# pavapro3.net
KiCad netlist of a schematic drawn in EAGLE
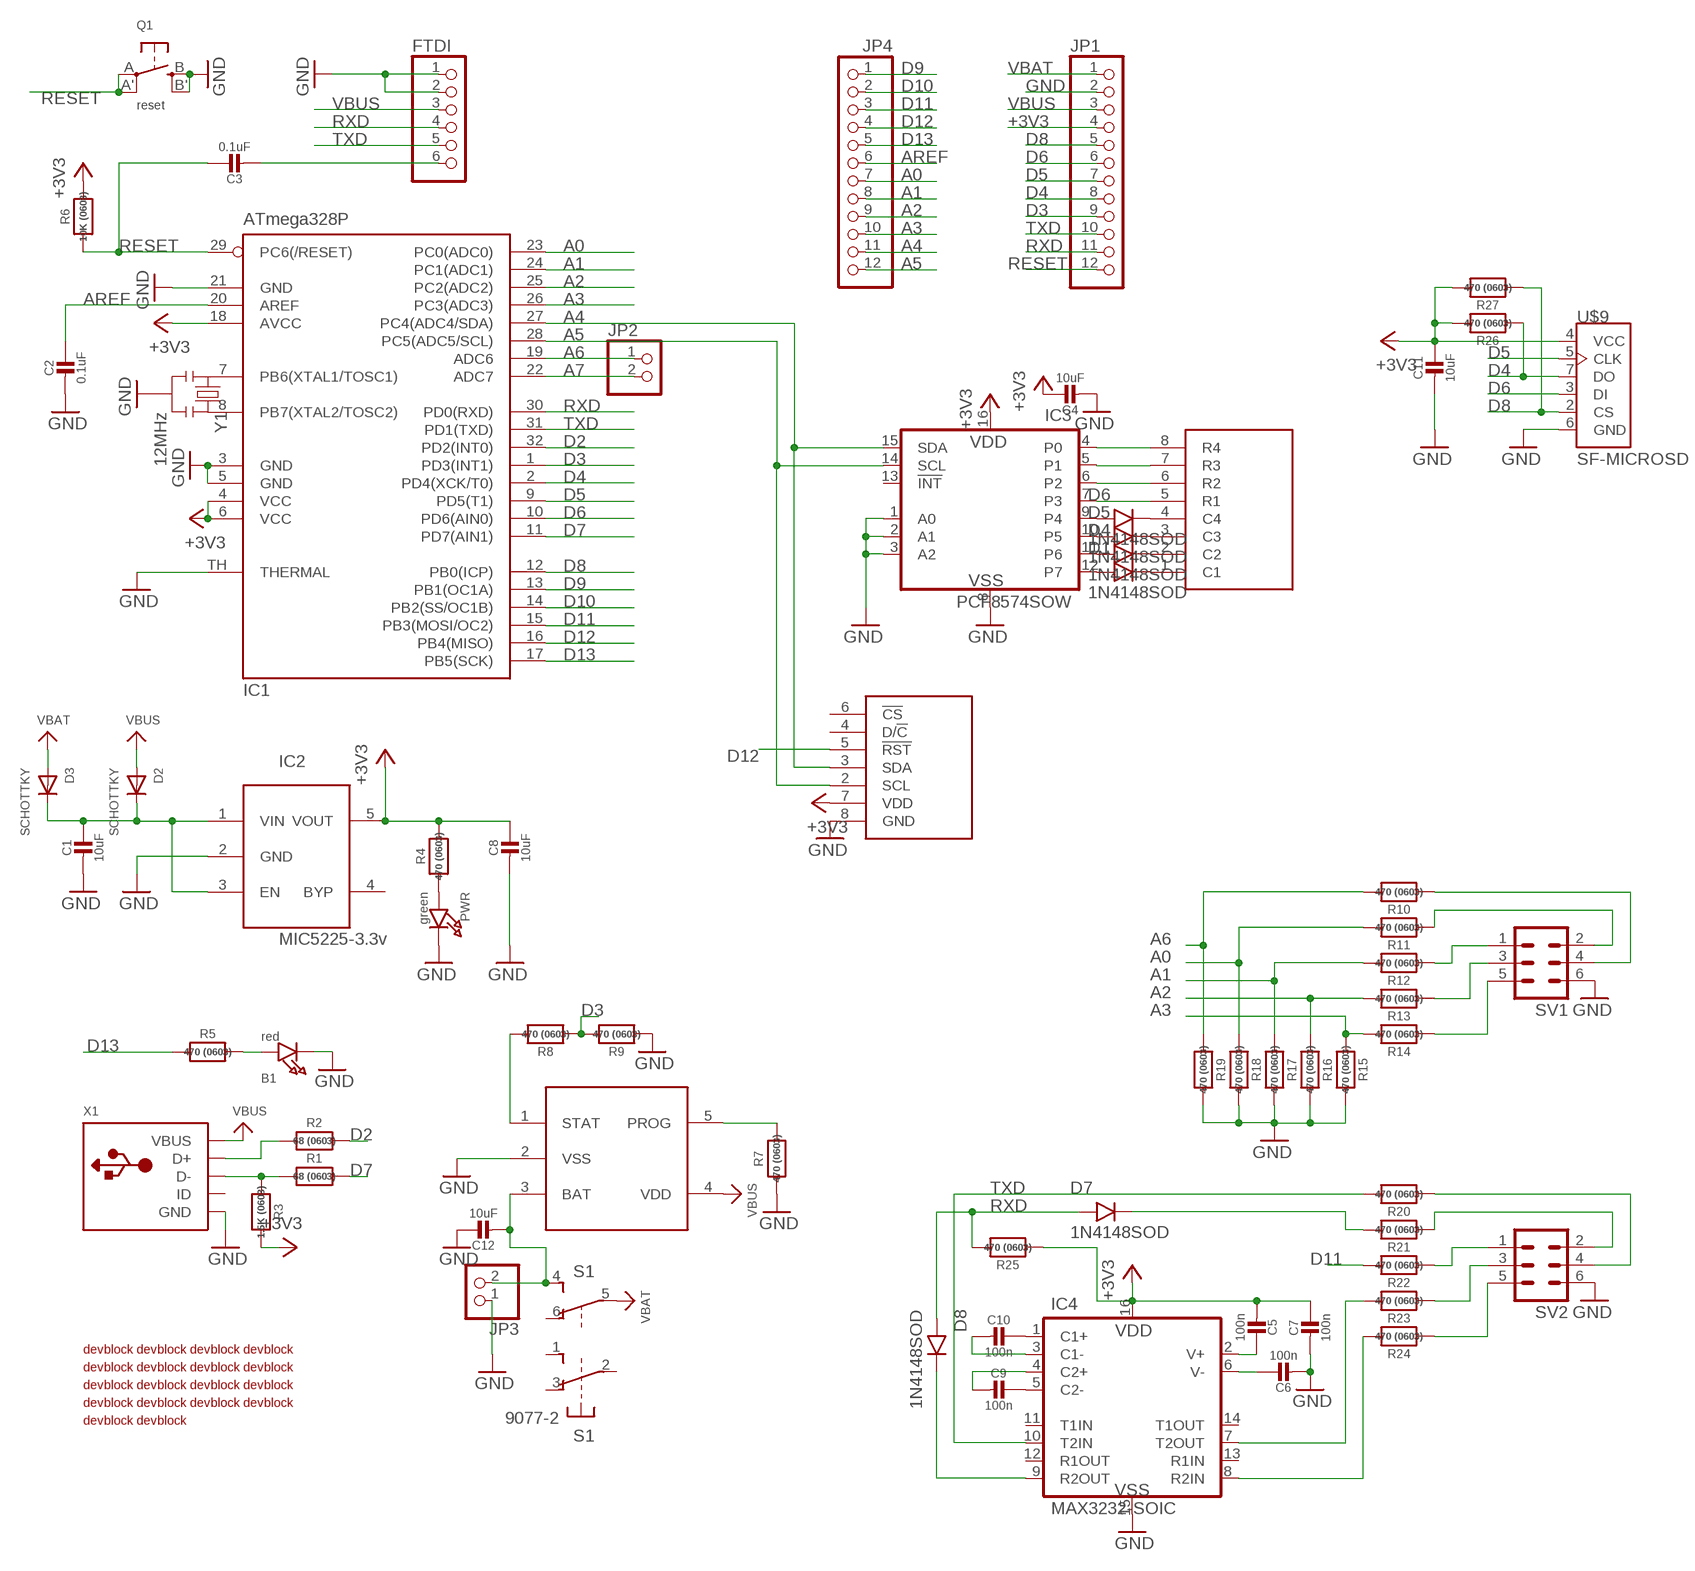
[diagram p0: schematic, sheet 1]

(export (version "E")
  (design (tool "Eeschema 10.0.6"))
  (components
    (comp (ref "B1")
      (value "red")
      (footprint "eagle-import:CHIPLED_0805_NOOUTLINE")
      (libsource (lib "eagle-import") (part "LED0805_NOOUTLINE"))
    )
    (comp (ref "C1")
      (value "10uF")
      (footprint "eagle-import:0805-NO")
      (libsource (lib "eagle-import") (part "CAP_CERAMIC0805-NOOUTLINE"))
    )
    (comp (ref "C2")
      (value "0.1uF")
      (footprint "eagle-import:_0805MP")
      (libsource (lib "eagle-import") (part "CAP_CERAMIC_0805MP"))
    )
    (comp (ref "C3")
      (value "0.1uF")
      (footprint "eagle-import:0805-NO")
      (libsource (lib "eagle-import") (part "CAP_CERAMIC0805-NOOUTLINE"))
    )
    (comp (ref "C4")
      (value "10uF")
      (footprint "eagle-import:0805-NO")
      (libsource (lib "eagle-import") (part "CAP_CERAMIC0805-NOOUTLINE"))
    )
    (comp (ref "C5")
      (value "100n")
      (footprint "eagle-import:0805-NO")
      (libsource (lib "eagle-import") (part "CAP_CERAMIC0805-NOOUTLINE"))
    )
    (comp (ref "C6")
      (value "100n")
      (footprint "eagle-import:0805-NO")
      (libsource (lib "eagle-import") (part "CAP_CERAMIC0805-NOOUTLINE"))
    )
    (comp (ref "C7")
      (value "100n")
      (footprint "eagle-import:0805-NO")
      (libsource (lib "eagle-import") (part "CAP_CERAMIC0805-NOOUTLINE"))
    )
    (comp (ref "C8")
      (value "10uF")
      (footprint "eagle-import:0805-NO")
      (libsource (lib "eagle-import") (part "CAP_CERAMIC0805-NOOUTLINE"))
    )
    (comp (ref "C9")
      (value "100n")
      (footprint "eagle-import:0805-NO")
      (libsource (lib "eagle-import") (part "CAP_CERAMIC0805-NOOUTLINE"))
    )
    (comp (ref "C10")
      (value "100n")
      (footprint "eagle-import:0805-NO")
      (libsource (lib "eagle-import") (part "CAP_CERAMIC0805-NOOUTLINE"))
    )
    (comp (ref "C11")
      (value "10uF")
      (footprint "eagle-import:0805-NO")
      (libsource (lib "eagle-import") (part "CAP_CERAMIC0805-NOOUTLINE"))
    )
    (comp (ref "C12")
      (value "10uF")
      (footprint "eagle-import:0805-NO")
      (libsource (lib "eagle-import") (part "CAP_CERAMIC0805-NOOUTLINE"))
    )
    (comp (ref "D1")
      (value "1N4148SOD")
      (footprint "eagle-import:SOD-80")
      (libsource (lib "eagle-import") (part "1N4148SOD"))
    )
    (comp (ref "D2")
      (value "SCHOTTKY")
      (footprint "eagle-import:ADAFRUIT_SOD-123FL")
      (libsource (lib "eagle-import") (part "ADAFRUIT_DIODE_SOD-123FL"))
    )
    (comp (ref "D3")
      (value "SCHOTTKY")
      (footprint "eagle-import:ADAFRUIT_SOD-123FL")
      (libsource (lib "eagle-import") (part "ADAFRUIT_DIODE_SOD-123FL"))
    )
    (comp (ref "D4")
      (value "1N4148SOD")
      (footprint "eagle-import:SOD-80")
      (libsource (lib "eagle-import") (part "1N4148SOD"))
    )
    (comp (ref "D5")
      (value "1N4148SOD")
      (footprint "eagle-import:SOD-80")
      (libsource (lib "eagle-import") (part "1N4148SOD"))
    )
    (comp (ref "D6")
      (value "1N4148SOD")
      (footprint "eagle-import:SOD-80")
      (libsource (lib "eagle-import") (part "1N4148SOD"))
    )
    (comp (ref "D7")
      (value "1N4148SOD")
      (footprint "eagle-import:SOD-80")
      (libsource (lib "eagle-import") (part "1N4148SOD"))
    )
    (comp (ref "D8")
      (value "1N4148SOD")
      (footprint "eagle-import:SOD-80")
      (libsource (lib "eagle-import") (part "1N4148SOD"))
    )
    (comp (ref "FTDI")
      (value "ADAFRUIT_PINHD-1X6CB")
      (footprint "eagle-import:ADAFRUIT_1X06-CLEANBIG")
      (libsource (lib "eagle-import") (part "ADAFRUIT_PINHD-1X6CB"))
    )
    (comp (ref "IC1")
      (value "ATmega328P")
      (footprint "eagle-import:MLF32-TH")
      (fields (field (name "MPN") "ATMEGA88PA-MU"))
      (libsource (lib "eagle-import") (part "MEGA8-MI"))
    )
    (comp (ref "IC2")
      (value "MIC5225-3.3v")
      (footprint "eagle-import:SOT23-5L")
      (libsource (lib "eagle-import") (part "LP298XS"))
    )
    (comp (ref "IC3")
      (value "PCF8574SOW")
      (footprint "eagle-import:SO-16DW")
      (libsource (lib "eagle-import") (part "PCF8574SOW"))
    )
    (comp (ref "IC4")
      (value "MAX3232-SOIC")
      (footprint "eagle-import:SO-16")
      (libsource (lib "eagle-import") (part "MAX3232-SOIC"))
    )
    (comp (ref "JP1")
      (value "ADAFRUIT_PINHD-1X12-CB")
      (footprint "eagle-import:ADAFRUIT_1X12-CB")
      (libsource (lib "eagle-import") (part "ADAFRUIT_PINHD-1X12-CB"))
    )
    (comp (ref "JP2")
      (value "HEADER-1X2ROUND")
      (footprint "eagle-import:1X02_ROUND")
      (libsource (lib "eagle-import") (part "HEADER-1X2ROUND"))
    )
    (comp (ref "JP3")
      (value "PINHD-1X02_2.54-90°")
      (footprint "eagle-import:1X02_90")
      (libsource (lib "eagle-import") (part "PINHD-1X02_2.54-90°"))
    )
    (comp (ref "JP4")
      (value "ADAFRUIT_PINHD-1X12-CB")
      (footprint "eagle-import:ADAFRUIT_1X12-CB")
      (libsource (lib "eagle-import") (part "ADAFRUIT_PINHD-1X12-CB"))
    )
    (comp (ref "PWR")
      (value "green")
      (footprint "eagle-import:CHIPLED_0805_NOOUTLINE")
      (libsource (lib "eagle-import") (part "LED0805_NOOUTLINE"))
    )
    (comp (ref "Q1")
      (value "reset")
      (footprint "eagle-import:BTN_KMR2_4.6X2.8")
      (libsource (lib "eagle-import") (part "SWITCH_TACT_SMT4.6X2.8"))
    )
    (comp (ref "R1")
      (value "68 (0603)")
      (footprint "eagle-import:0603-NO")
      (libsource (lib "eagle-import") (part "RESISTOR_0603_NOOUT"))
    )
    (comp (ref "R2")
      (value "68 (0603)")
      (footprint "eagle-import:0603-NO")
      (libsource (lib "eagle-import") (part "RESISTOR_0603_NOOUT"))
    )
    (comp (ref "R3")
      (value "1.5K (0603)")
      (footprint "eagle-import:0603-NO")
      (libsource (lib "eagle-import") (part "RESISTOR_0603_NOOUT"))
    )
    (comp (ref "R4")
      (value "470 (0603)")
      (footprint "eagle-import:0603-NO")
      (libsource (lib "eagle-import") (part "RESISTOR_0603_NOOUT"))
    )
    (comp (ref "R5")
      (value "470 (0603)")
      (footprint "eagle-import:0603-NO")
      (libsource (lib "eagle-import") (part "RESISTOR_0603_NOOUT"))
    )
    (comp (ref "R6")
      (value "10K (0603)")
      (footprint "eagle-import:0805-NO")
      (libsource (lib "eagle-import") (part "RESISTOR0805_NOOUTLINE"))
    )
    (comp (ref "R7")
      (value "470 (0603)")
      (footprint "eagle-import:_0805")
      (libsource (lib "eagle-import") (part "RESISTOR_0805"))
    )
    (comp (ref "R8")
      (value "470 (0603)")
      (footprint "eagle-import:_0805")
      (libsource (lib "eagle-import") (part "RESISTOR_0805"))
    )
    (comp (ref "R9")
      (value "470 (0603)")
      (footprint "eagle-import:_0805")
      (libsource (lib "eagle-import") (part "RESISTOR_0805"))
    )
    (comp (ref "R10")
      (value "470 (0603)")
      (footprint "eagle-import:_0805")
      (libsource (lib "eagle-import") (part "RESISTOR_0805"))
    )
    (comp (ref "R11")
      (value "470 (0603)")
      (footprint "eagle-import:_0805")
      (libsource (lib "eagle-import") (part "RESISTOR_0805"))
    )
    (comp (ref "R12")
      (value "470 (0603)")
      (footprint "eagle-import:_0805")
      (libsource (lib "eagle-import") (part "RESISTOR_0805"))
    )
    (comp (ref "R13")
      (value "470 (0603)")
      (footprint "eagle-import:_0805")
      (libsource (lib "eagle-import") (part "RESISTOR_0805"))
    )
    (comp (ref "R14")
      (value "470 (0603)")
      (footprint "eagle-import:_0805")
      (libsource (lib "eagle-import") (part "RESISTOR_0805"))
    )
    (comp (ref "R15")
      (value "470 (0603)")
      (footprint "eagle-import:_0805")
      (libsource (lib "eagle-import") (part "RESISTOR_0805"))
    )
    (comp (ref "R16")
      (value "470 (0603)")
      (footprint "eagle-import:_0805")
      (libsource (lib "eagle-import") (part "RESISTOR_0805"))
    )
    (comp (ref "R17")
      (value "470 (0603)")
      (footprint "eagle-import:_0805")
      (libsource (lib "eagle-import") (part "RESISTOR_0805"))
    )
    (comp (ref "R18")
      (value "470 (0603)")
      (footprint "eagle-import:_0805")
      (libsource (lib "eagle-import") (part "RESISTOR_0805"))
    )
    (comp (ref "R19")
      (value "470 (0603)")
      (footprint "eagle-import:_0805")
      (libsource (lib "eagle-import") (part "RESISTOR_0805"))
    )
    (comp (ref "R20")
      (value "470 (0603)")
      (footprint "eagle-import:_0805")
      (libsource (lib "eagle-import") (part "RESISTOR_0805"))
    )
    (comp (ref "R21")
      (value "470 (0603)")
      (footprint "eagle-import:_0805")
      (libsource (lib "eagle-import") (part "RESISTOR_0805"))
    )
    (comp (ref "R22")
      (value "470 (0603)")
      (footprint "eagle-import:_0805")
      (libsource (lib "eagle-import") (part "RESISTOR_0805"))
    )
    (comp (ref "R23")
      (value "470 (0603)")
      (footprint "eagle-import:_0805")
      (libsource (lib "eagle-import") (part "RESISTOR_0805"))
    )
    (comp (ref "R24")
      (value "470 (0603)")
      (footprint "eagle-import:_0805")
      (libsource (lib "eagle-import") (part "RESISTOR_0805"))
    )
    (comp (ref "R25")
      (value "470 (0603)")
      (footprint "eagle-import:_0805")
      (libsource (lib "eagle-import") (part "RESISTOR_0805"))
    )
    (comp (ref "R26")
      (value "470 (0603)")
      (footprint "eagle-import:_0805")
      (libsource (lib "eagle-import") (part "RESISTOR_0805"))
    )
    (comp (ref "R27")
      (value "470 (0603)")
      (footprint "eagle-import:_0805")
      (libsource (lib "eagle-import") (part "RESISTOR_0805"))
    )
    (comp (ref "S1")
      (value "9077-2")
      (footprint "eagle-import:9077-2")
      (libsource (lib "eagle-import") (part "9077-2"))
    )
    (comp (ref "SV1")
      (value "ML6")
      (footprint "eagle-import:ML6")
      (libsource (lib "eagle-import") (part "ML6"))
    )
    (comp (ref "SV2")
      (value "ML6")
      (footprint "eagle-import:ML6")
      (libsource (lib "eagle-import") (part "ML6"))
    )
    (comp (ref "U$5")
      (value "DISP_OLED_2864")
      (footprint "eagle-import:OLED2864")
      (libsource (lib "eagle-import") (part "DISP_OLED_2864"))
    )
    (comp (ref "U$6")
      (value "MCP73831")
      (footprint "eagle-import:SOT23-5")
      (libsource (lib "eagle-import") (part "MCP73831"))
    )
    (comp (ref "U$7")
      (value "KB1604")
      (footprint "eagle-import:KB1604")
      (libsource (lib "eagle-import") (part "KB1604"))
    )
    (comp (ref "U$9")
      (value "SF-MICROSD")
      (footprint "eagle-import:MICROSD")
      (libsource (lib "eagle-import") (part "SF-MICROSD"))
    )
    (comp (ref "U$10")
      (value "DEVBLOCK_1_16")
      (footprint "eagle-import:DEVBLOCK_1_16")
      (libsource (lib "eagle-import") (part "DEVBLOCK_1_16"))
    )
    (comp (ref "U$11")
      (value "DEVBLOCK_1_16")
      (footprint "eagle-import:DEVBLOCK_1_16")
      (libsource (lib "eagle-import") (part "DEVBLOCK_1_16"))
    )
    (comp (ref "U$12")
      (value "DEVBLOCK_1_16")
      (footprint "eagle-import:DEVBLOCK_1_16")
      (libsource (lib "eagle-import") (part "DEVBLOCK_1_16"))
    )
    (comp (ref "U$13")
      (value "DEVBLOCK_1_16")
      (footprint "eagle-import:DEVBLOCK_1_16")
      (libsource (lib "eagle-import") (part "DEVBLOCK_1_16"))
    )
    (comp (ref "U$14")
      (value "DEVBLOCK_1_16")
      (footprint "eagle-import:DEVBLOCK_1_16")
      (libsource (lib "eagle-import") (part "DEVBLOCK_1_16"))
    )
    (comp (ref "U$15")
      (value "DEVBLOCK_1_16")
      (footprint "eagle-import:DEVBLOCK_1_16")
      (libsource (lib "eagle-import") (part "DEVBLOCK_1_16"))
    )
    (comp (ref "U$16")
      (value "DEVBLOCK_1_16")
      (footprint "eagle-import:DEVBLOCK_1_16")
      (libsource (lib "eagle-import") (part "DEVBLOCK_1_16"))
    )
    (comp (ref "U$17")
      (value "DEVBLOCK_1_16")
      (footprint "eagle-import:DEVBLOCK_1_16")
      (libsource (lib "eagle-import") (part "DEVBLOCK_1_16"))
    )
    (comp (ref "U$18")
      (value "DEVBLOCK_1_16")
      (footprint "eagle-import:DEVBLOCK_1_16")
      (libsource (lib "eagle-import") (part "DEVBLOCK_1_16"))
    )
    (comp (ref "U$19")
      (value "DEVBLOCK_1_16")
      (footprint "eagle-import:DEVBLOCK_1_16")
      (libsource (lib "eagle-import") (part "DEVBLOCK_1_16"))
    )
    (comp (ref "U$20")
      (value "DEVBLOCK_1_16")
      (footprint "eagle-import:DEVBLOCK_1_16")
      (libsource (lib "eagle-import") (part "DEVBLOCK_1_16"))
    )
    (comp (ref "U$21")
      (value "DEVBLOCK_1_16")
      (footprint "eagle-import:DEVBLOCK_1_16")
      (libsource (lib "eagle-import") (part "DEVBLOCK_1_16"))
    )
    (comp (ref "U$22")
      (value "DEVBLOCK_1_16")
      (footprint "eagle-import:DEVBLOCK_1_16")
      (libsource (lib "eagle-import") (part "DEVBLOCK_1_16"))
    )
    (comp (ref "U$23")
      (value "DEVBLOCK_1_16")
      (footprint "eagle-import:DEVBLOCK_1_16")
      (libsource (lib "eagle-import") (part "DEVBLOCK_1_16"))
    )
    (comp (ref "U$24")
      (value "DEVBLOCK_1_16")
      (footprint "eagle-import:DEVBLOCK_1_16")
      (libsource (lib "eagle-import") (part "DEVBLOCK_1_16"))
    )
    (comp (ref "U$25")
      (value "DEVBLOCK_1_16")
      (footprint "eagle-import:DEVBLOCK_1_16")
      (libsource (lib "eagle-import") (part "DEVBLOCK_1_16"))
    )
    (comp (ref "U$26")
      (value "DEVBLOCK_1_16")
      (footprint "eagle-import:DEVBLOCK_1_16")
      (libsource (lib "eagle-import") (part "DEVBLOCK_1_16"))
    )
    (comp (ref "U$27")
      (value "DEVBLOCK_1_16")
      (footprint "eagle-import:DEVBLOCK_1_16")
      (libsource (lib "eagle-import") (part "DEVBLOCK_1_16"))
    )
    (comp (ref "X1")
      (value "MICROBUILDER_USBMICRO_20329")
      (footprint "eagle-import:MICROBUILDER_4UCONN_20329")
      (libsource (lib "eagle-import") (part "MICROBUILDER_USBMICRO_20329"))
    )
    (comp (ref "Y1")
      (value "12MHz")
      (footprint "eagle-import:RESONATOR-SMD")
      (libsource (lib "eagle-import") (part "RESONATORSMD"))
    )
  )
  (nets
    (net (code "1") (name "+3V3") (class "Default")
      (node (ref "C11") (pin "1") (pinfunction "1_1") (pintype "passive"))
      (node (ref "C4") (pin "1") (pinfunction "1_1") (pintype "passive"))
      (node (ref "C5") (pin "2") (pinfunction "2_2") (pintype "passive"))
      (node (ref "C7") (pin "1") (pinfunction "1_1") (pintype "passive"))
      (node (ref "C8") (pin "1") (pinfunction "1_1") (pintype "passive"))
      (node (ref "IC1") (pin "18") (pinfunction "AVCC_18") (pintype "power_in"))
      (node (ref "IC1") (pin "4") (pinfunction "VCC_4") (pintype "power_in"))
      (node (ref "IC1") (pin "6") (pinfunction "VCC_6") (pintype "power_in"))
      (node (ref "IC2") (pin "5") (pinfunction "VOUT_5") (pintype "bidirectional"))
      (node (ref "IC3") (pin "16") (pinfunction "VDD_16") (pintype "power_in"))
      (node (ref "IC4") (pin "16") (pinfunction "VDD_16") (pintype "power_in"))
      (node (ref "JP1") (pin "4") (pinfunction "4_4") (pintype "passive"))
      (node (ref "R25") (pin "2") (pinfunction "2_2") (pintype "passive"))
      (node (ref "R26") (pin "1") (pinfunction "1_1") (pintype "passive"))
      (node (ref "R27") (pin "1") (pinfunction "1_1") (pintype "passive"))
      (node (ref "R3") (pin "2") (pinfunction "2_2") (pintype "passive"))
      (node (ref "R4") (pin "2") (pinfunction "2_2") (pintype "passive"))
      (node (ref "R6") (pin "2") (pinfunction "2_2") (pintype "passive"))
      (node (ref "U$5") (pin "7") (pinfunction "VDD_7") (pintype "bidirectional"))
      (node (ref "U$9") (pin "4") (pinfunction "VCC_4") (pintype "passive"))
    )
    (net (code "2") (name "/A0") (class "Default")
      (node (ref "IC1") (pin "23") (pinfunction "PC0(ADC0)_23") (pintype "bidirectional"))
      (node (ref "JP4") (pin "7") (pinfunction "7_7") (pintype "passive"))
      (node (ref "R11") (pin "1") (pinfunction "1_1") (pintype "passive"))
      (node (ref "R18") (pin "2") (pinfunction "2_2") (pintype "passive"))
    )
    (net (code "3") (name "/A1") (class "Default")
      (node (ref "IC1") (pin "24") (pinfunction "PC1(ADC1)_24") (pintype "bidirectional"))
      (node (ref "JP4") (pin "8") (pinfunction "8_8") (pintype "passive"))
      (node (ref "R12") (pin "1") (pinfunction "1_1") (pintype "passive"))
      (node (ref "R17") (pin "2") (pinfunction "2_2") (pintype "passive"))
    )
    (net (code "4") (name "/A2") (class "Default")
      (node (ref "IC1") (pin "25") (pinfunction "PC2(ADC2)_25") (pintype "bidirectional"))
      (node (ref "JP4") (pin "9") (pinfunction "9_9") (pintype "passive"))
      (node (ref "R13") (pin "1") (pinfunction "1_1") (pintype "passive"))
      (node (ref "R16") (pin "2") (pinfunction "2_2") (pintype "passive"))
    )
    (net (code "5") (name "/A3") (class "Default")
      (node (ref "IC1") (pin "26") (pinfunction "PC3(ADC3)_26") (pintype "bidirectional"))
      (node (ref "JP4") (pin "10") (pinfunction "10_10") (pintype "passive"))
      (node (ref "R14") (pin "1") (pinfunction "1_1") (pintype "passive"))
      (node (ref "R15") (pin "2") (pinfunction "2_2") (pintype "passive"))
    )
    (net (code "6") (name "/A4") (class "Default")
      (node (ref "IC1") (pin "27") (pinfunction "PC4(ADC4/SDA)_27") (pintype "bidirectional"))
      (node (ref "IC3") (pin "15") (pinfunction "SDA_15") (pintype "bidirectional"))
      (node (ref "JP4") (pin "11") (pinfunction "11_11") (pintype "passive"))
      (node (ref "U$5") (pin "3") (pinfunction "SDA_3") (pintype "bidirectional"))
    )
    (net (code "7") (name "/A5") (class "Default")
      (node (ref "IC1") (pin "28") (pinfunction "PC5(ADC5/SCL)_28") (pintype "bidirectional"))
      (node (ref "IC3") (pin "14") (pinfunction "SCL_14") (pintype "bidirectional"))
      (node (ref "JP4") (pin "12") (pinfunction "12_12") (pintype "passive"))
      (node (ref "U$5") (pin "2") (pinfunction "SCL_2") (pintype "bidirectional"))
    )
    (net (code "8") (name "/A6") (class "Default")
      (node (ref "IC1") (pin "19") (pinfunction "ADC6_19") (pintype "bidirectional"))
      (node (ref "JP2") (pin "1") (pinfunction "1_1") (pintype "passive"))
      (node (ref "R10") (pin "1") (pinfunction "1_1") (pintype "passive"))
      (node (ref "R19") (pin "2") (pinfunction "2_2") (pintype "passive"))
    )
    (net (code "9") (name "/A7") (class "Default")
      (node (ref "IC1") (pin "22") (pinfunction "ADC7_22") (pintype "bidirectional"))
      (node (ref "JP2") (pin "2") (pinfunction "2_2") (pintype "passive"))
    )
    (net (code "10") (name "/AREF") (class "Default")
      (node (ref "C2") (pin "1") (pinfunction "1_1") (pintype "passive"))
      (node (ref "IC1") (pin "20") (pinfunction "AREF_20") (pintype "passive"))
      (node (ref "JP4") (pin "6") (pinfunction "6_6") (pintype "passive"))
    )
    (net (code "11") (name "/D2") (class "Default")
      (node (ref "IC1") (pin "32") (pinfunction "PD2(INT0)_32") (pintype "bidirectional"))
      (node (ref "R2") (pin "2") (pinfunction "2_2") (pintype "passive"))
    )
    (net (code "12") (name "/D3") (class "Default")
      (node (ref "IC1") (pin "1") (pinfunction "PD3(INT1)_1") (pintype "bidirectional"))
      (node (ref "JP1") (pin "9") (pinfunction "9_9") (pintype "passive"))
      (node (ref "R8") (pin "2") (pinfunction "2_2") (pintype "passive"))
      (node (ref "R9") (pin "1") (pinfunction "1_1") (pintype "passive"))
    )
    (net (code "13") (name "/D4") (class "Default")
      (node (ref "IC1") (pin "2") (pinfunction "PD4(XCK/T0)_2") (pintype "bidirectional"))
      (node (ref "JP1") (pin "8") (pinfunction "8_8") (pintype "passive"))
      (node (ref "R26") (pin "2") (pinfunction "2_2") (pintype "passive"))
      (node (ref "U$9") (pin "7") (pinfunction "DO_7") (pintype "bidirectional"))
    )
    (net (code "14") (name "/D5") (class "Default")
      (node (ref "IC1") (pin "9") (pinfunction "PD5(T1)_9") (pintype "bidirectional"))
      (node (ref "JP1") (pin "7") (pinfunction "7_7") (pintype "passive"))
      (node (ref "U$9") (pin "5") (pinfunction "CLK_5") (pintype "bidirectional"))
    )
    (net (code "15") (name "/D6") (class "Default")
      (node (ref "IC1") (pin "10") (pinfunction "PD6(AIN0)_10") (pintype "bidirectional"))
      (node (ref "JP1") (pin "6") (pinfunction "6_6") (pintype "passive"))
      (node (ref "U$9") (pin "3") (pinfunction "DI_3") (pintype "bidirectional"))
    )
    (net (code "16") (name "/D7") (class "Default")
      (node (ref "IC1") (pin "11") (pinfunction "PD7(AIN1)_11") (pintype "bidirectional"))
      (node (ref "R1") (pin "2") (pinfunction "2_2") (pintype "passive"))
    )
    (net (code "17") (name "/D8") (class "Default")
      (node (ref "IC1") (pin "12") (pinfunction "PB0(ICP)_12") (pintype "bidirectional"))
      (node (ref "JP1") (pin "5") (pinfunction "5_5") (pintype "passive"))
      (node (ref "R27") (pin "2") (pinfunction "2_2") (pintype "passive"))
      (node (ref "U$9") (pin "2") (pinfunction "CS_2") (pintype "bidirectional"))
    )
    (net (code "18") (name "/D9") (class "Default")
      (node (ref "IC1") (pin "13") (pinfunction "PB1(OC1A)_13") (pintype "bidirectional"))
      (node (ref "JP4") (pin "1") (pinfunction "1_1") (pintype "passive"))
    )
    (net (code "19") (name "/D10") (class "Default")
      (node (ref "IC1") (pin "14") (pinfunction "PB2(SS/OC1B)_14") (pintype "bidirectional"))
      (node (ref "JP4") (pin "2") (pinfunction "2_2") (pintype "passive"))
    )
    (net (code "20") (name "/D11") (class "Default")
      (node (ref "IC1") (pin "15") (pinfunction "PB3(MOSI/OC2)_15") (pintype "bidirectional"))
      (node (ref "JP4") (pin "3") (pinfunction "3_3") (pintype "passive"))
      (node (ref "R22") (pin "1") (pinfunction "1_1") (pintype "passive"))
    )
    (net (code "21") (name "/D12") (class "Default")
      (node (ref "IC1") (pin "16") (pinfunction "PB4(MISO)_16") (pintype "bidirectional"))
      (node (ref "JP4") (pin "4") (pinfunction "4_4") (pintype "passive"))
      (node (ref "U$5") (pin "5") (pinfunction "~{RST}_5") (pintype "bidirectional"))
    )
    (net (code "22") (name "/D13") (class "Default")
      (node (ref "IC1") (pin "17") (pinfunction "PB5(SCK)_17") (pintype "bidirectional"))
      (node (ref "JP4") (pin "5") (pinfunction "5_5") (pintype "passive"))
      (node (ref "R5") (pin "2") (pinfunction "2_2") (pintype "passive"))
    )
    (net (code "23") (name "/RESET") (class "Default")
      (node (ref "C3") (pin "1") (pinfunction "1_1") (pintype "passive"))
      (node (ref "IC1") (pin "29") (pinfunction "PC6(/RESET)_29") (pintype "bidirectional"))
      (node (ref "JP1") (pin "12") (pinfunction "12_12") (pintype "passive"))
      (node (ref "Q1") (pin "A") (pinfunction "P_A") (pintype "passive"))
      (node (ref "Q1") (pin "A'") (pinfunction "P1_A'") (pintype "passive"))
      (node (ref "R6") (pin "1") (pinfunction "1_1") (pintype "passive"))
    )
    (net (code "24") (name "/RXD") (class "Default")
      (node (ref "D7") (pin "A") (pinfunction "A_A") (pintype "input"))
      (node (ref "D8") (pin "A") (pinfunction "A_A") (pintype "input"))
      (node (ref "FTDI") (pin "4") (pinfunction "4_4") (pintype "passive"))
      (node (ref "IC1") (pin "30") (pinfunction "PD0(RXD)_30") (pintype "bidirectional"))
      (node (ref "JP1") (pin "11") (pinfunction "11_11") (pintype "passive"))
      (node (ref "R25") (pin "1") (pinfunction "1_1") (pintype "passive"))
    )
    (net (code "25") (name "/TXD") (class "Default")
      (node (ref "FTDI") (pin "5") (pinfunction "5_5") (pintype "passive"))
      (node (ref "IC1") (pin "31") (pinfunction "PD1(TXD)_31") (pintype "bidirectional"))
      (node (ref "IC4") (pin "10") (pinfunction "T2IN_10") (pintype "input"))
      (node (ref "JP1") (pin "10") (pinfunction "10_10") (pintype "passive"))
      (node (ref "R20") (pin "1") (pinfunction "1_1") (pintype "passive"))
    )
    (net (code "26") (name "GND") (class "Default")
      (node (ref "B1") (pin "C") (pinfunction "C_C") (pintype "passive"))
      (node (ref "C1") (pin "2") (pinfunction "2_2") (pintype "passive"))
      (node (ref "C11") (pin "2") (pinfunction "2_2") (pintype "passive"))
      (node (ref "C12") (pin "1") (pinfunction "1_1") (pintype "passive"))
      (node (ref "C2") (pin "2") (pinfunction "2_2") (pintype "passive"))
      (node (ref "C4") (pin "2") (pinfunction "2_2") (pintype "passive"))
      (node (ref "C6") (pin "2") (pinfunction "2_2") (pintype "passive"))
      (node (ref "C7") (pin "2") (pinfunction "2_2") (pintype "passive"))
      (node (ref "C8") (pin "2") (pinfunction "2_2") (pintype "passive"))
      (node (ref "FTDI") (pin "1") (pinfunction "1_1") (pintype "passive"))
      (node (ref "FTDI") (pin "2") (pinfunction "2_2") (pintype "passive"))
      (node (ref "IC1") (pin "21") (pinfunction "GND_21") (pintype "power_in"))
      (node (ref "IC1") (pin "3") (pinfunction "GND_3") (pintype "power_in"))
      (node (ref "IC1") (pin "5") (pinfunction "GND_5") (pintype "power_in"))
      (node (ref "IC1") (pin "TH") (pinfunction "THERMAL_TH") (pintype "passive"))
      (node (ref "IC2") (pin "2") (pinfunction "GND_2") (pintype "bidirectional"))
      (node (ref "IC3") (pin "1") (pinfunction "A0_1") (pintype "bidirectional"))
      (node (ref "IC3") (pin "2") (pinfunction "A1_2") (pintype "bidirectional"))
      (node (ref "IC3") (pin "3") (pinfunction "A2_3") (pintype "bidirectional"))
      (node (ref "IC3") (pin "8") (pinfunction "VSS_8") (pintype "power_in"))
      (node (ref "IC4") (pin "15") (pinfunction "VSS_15") (pintype "power_in"))
      (node (ref "JP1") (pin "2") (pinfunction "2_2") (pintype "passive"))
      (node (ref "JP3") (pin "1") (pinfunction "1_1") (pintype "passive"))
      (node (ref "PWR") (pin "C") (pinfunction "C_C") (pintype "passive"))
      (node (ref "Q1") (pin "B") (pinfunction "S_B") (pintype "passive"))
      (node (ref "Q1") (pin "B'") (pinfunction "S1_B'") (pintype "passive"))
      (node (ref "R15") (pin "1") (pinfunction "1_1") (pintype "passive"))
      (node (ref "R16") (pin "1") (pinfunction "1_1") (pintype "passive"))
      (node (ref "R17") (pin "1") (pinfunction "1_1") (pintype "passive"))
      (node (ref "R18") (pin "1") (pinfunction "1_1") (pintype "passive"))
      (node (ref "R19") (pin "1") (pinfunction "1_1") (pintype "passive"))
      (node (ref "R7") (pin "2") (pinfunction "2_2") (pintype "passive"))
      (node (ref "R9") (pin "2") (pinfunction "2_2") (pintype "passive"))
      (node (ref "SV1") (pin "6") (pinfunction "6_6") (pintype "passive"))
      (node (ref "SV2") (pin "6") (pinfunction "6_6") (pintype "passive"))
      (node (ref "U$5") (pin "8") (pinfunction "GND_8") (pintype "bidirectional"))
      (node (ref "U$6") (pin "2") (pinfunction "VSS_2") (pintype "bidirectional"))
      (node (ref "U$9") (pin "6") (pinfunction "GND_6") (pintype "power_in"))
      (node (ref "X1") (pin "BASE@1") (pinfunction "GND_BASE@1") (pintype "power_in"))
      (node (ref "X1") (pin "BASE@2") (pinfunction "GND_BASE@2") (pintype "power_in"))
      (node (ref "X1") (pin "GND") (pinfunction "GND_GND") (pintype "power_in"))
      (node (ref "X1") (pin "SPRT@1") (pinfunction "GND_SPRT@1") (pintype "power_in"))
      (node (ref "X1") (pin "SPRT@2") (pinfunction "GND_SPRT@2") (pintype "power_in"))
      (node (ref "X1") (pin "SPRT@3") (pinfunction "GND_SPRT@3") (pintype "power_in"))
      (node (ref "X1") (pin "SPRT@4") (pinfunction "GND_SPRT@4") (pintype "power_in"))
      (node (ref "Y1") (pin "2") (pinfunction "2_2") (pintype "passive"))
    )
    (net (code "27") (name "Net-(B1-PadA)") (class "Default")
      (node (ref "B1") (pin "A") (pinfunction "A_A") (pintype "passive"))
      (node (ref "R5") (pin "1") (pinfunction "1_1") (pintype "passive"))
    )
    (net (code "28") (name "Net-(C3-Pad2)") (class "Default")
      (node (ref "C3") (pin "2") (pinfunction "2_2") (pintype "passive"))
      (node (ref "FTDI") (pin "6") (pinfunction "6_6") (pintype "passive"))
    )
    (net (code "29") (name "Net-(D7-PadK)") (class "Default")
      (node (ref "D7") (pin "K") (pinfunction "K_K") (pintype "output"))
      (node (ref "R21") (pin "1") (pinfunction "1_1") (pintype "passive"))
    )
    (net (code "30") (name "Net-(IC1-PB6(XTAL1{slash}TOSC1))") (class "Default")
      (node (ref "IC1") (pin "7") (pinfunction "PB6(XTAL1/TOSC1)_7") (pintype "bidirectional"))
      (node (ref "Y1") (pin "1") (pinfunction "1_1") (pintype "passive"))
    )
    (net (code "31") (name "Net-(IC1-PB7(XTAL2{slash}TOSC2))") (class "Default")
      (node (ref "IC1") (pin "8") (pinfunction "PB7(XTAL2/TOSC2)_8") (pintype "bidirectional"))
      (node (ref "Y1") (pin "3") (pinfunction "3_3") (pintype "passive"))
    )
    (net (code "32") (name "Net-(IC2-EN)") (class "Default")
      (node (ref "C1") (pin "1") (pinfunction "1_1") (pintype "passive"))
      (node (ref "D2") (pin "C") (pinfunction "C_C") (pintype "passive"))
      (node (ref "D3") (pin "C") (pinfunction "C_C") (pintype "passive"))
      (node (ref "IC2") (pin "1") (pinfunction "VIN_1") (pintype "bidirectional"))
      (node (ref "IC2") (pin "3") (pinfunction "EN_3") (pintype "bidirectional"))
    )
    (net (code "33") (name "Net-(IC3-P0)") (class "Default")
      (node (ref "IC3") (pin "4") (pinfunction "P0_4") (pintype "bidirectional"))
      (node (ref "U$7") (pin "8") (pinfunction "R4_8") (pintype "bidirectional"))
    )
    (net (code "34") (name "Net-(IC3-P1)") (class "Default")
      (node (ref "IC3") (pin "5") (pinfunction "P1_5") (pintype "bidirectional"))
      (node (ref "U$7") (pin "7") (pinfunction "R3_7") (pintype "bidirectional"))
    )
    (net (code "35") (name "Net-(IC3-P2)") (class "Default")
      (node (ref "IC3") (pin "6") (pinfunction "P2_6") (pintype "bidirectional"))
      (node (ref "U$7") (pin "6") (pinfunction "R2_6") (pintype "bidirectional"))
    )
    (net (code "36") (name "Net-(IC3-P3)") (class "Default")
      (node (ref "IC3") (pin "7") (pinfunction "P3_7") (pintype "bidirectional"))
      (node (ref "U$7") (pin "5") (pinfunction "R1_5") (pintype "bidirectional"))
    )
    (net (code "37") (name "Net-(IC3-P4)") (class "Default")
      (node (ref "D6") (pin "A") (pinfunction "A_A") (pintype "input"))
      (node (ref "IC3") (pin "9") (pinfunction "P4_9") (pintype "bidirectional"))
    )
    (net (code "38") (name "Net-(IC3-P5)") (class "Default")
      (node (ref "D5") (pin "A") (pinfunction "A_A") (pintype "input"))
      (node (ref "IC3") (pin "10") (pinfunction "P5_10") (pintype "bidirectional"))
    )
    (net (code "39") (name "Net-(IC3-P6)") (class "Default")
      (node (ref "D4") (pin "A") (pinfunction "A_A") (pintype "input"))
      (node (ref "IC3") (pin "11") (pinfunction "P6_11") (pintype "bidirectional"))
    )
    (net (code "40") (name "Net-(IC3-P7)") (class "Default")
      (node (ref "D1") (pin "A") (pinfunction "A_A") (pintype "input"))
      (node (ref "IC3") (pin "12") (pinfunction "P7_12") (pintype "bidirectional"))
    )
    (net (code "41") (name "Net-(IC4-C1+)") (class "Default")
      (node (ref "C10") (pin "1") (pinfunction "1_1") (pintype "passive"))
      (node (ref "IC4") (pin "1") (pinfunction "C1+_1") (pintype "bidirectional"))
    )
    (net (code "42") (name "Net-(IC4-C1-)") (class "Default")
      (node (ref "C10") (pin "2") (pinfunction "2_2") (pintype "passive"))
      (node (ref "IC4") (pin "3") (pinfunction "C1-_3") (pintype "bidirectional"))
    )
    (net (code "43") (name "Net-(IC4-C2+)") (class "Default")
      (node (ref "C9") (pin "2") (pinfunction "2_2") (pintype "passive"))
      (node (ref "IC4") (pin "4") (pinfunction "C2+_4") (pintype "bidirectional"))
    )
    (net (code "44") (name "Net-(IC4-C2-)") (class "Default")
      (node (ref "C9") (pin "1") (pinfunction "1_1") (pintype "passive"))
      (node (ref "IC4") (pin "5") (pinfunction "C2-_5") (pintype "bidirectional"))
    )
    (net (code "45") (name "Net-(IC4-R2IN)") (class "Default")
      (node (ref "IC4") (pin "8") (pinfunction "R2IN_8") (pintype "output"))
      (node (ref "R24") (pin "1") (pinfunction "1_1") (pintype "passive"))
    )
    (net (code "46") (name "Net-(IC4-R2OUT)") (class "Default")
      (node (ref "D8") (pin "K") (pinfunction "K_K") (pintype "output"))
      (node (ref "IC4") (pin "9") (pinfunction "R2OUT_9") (pintype "input"))
    )
    (net (code "47") (name "Net-(IC4-T2OUT)") (class "Default")
      (node (ref "IC4") (pin "7") (pinfunction "T2OUT_7") (pintype "output"))
      (node (ref "R23") (pin "1") (pinfunction "1_1") (pintype "passive"))
    )
    (net (code "48") (name "Net-(IC4-V+)") (class "Default")
      (node (ref "C5") (pin "1") (pinfunction "1_1") (pintype "passive"))
      (node (ref "IC4") (pin "2") (pinfunction "V+_2") (pintype "bidirectional"))
    )
    (net (code "49") (name "Net-(IC4-V-)") (class "Default")
      (node (ref "C6") (pin "1") (pinfunction "1_1") (pintype "passive"))
      (node (ref "IC4") (pin "6") (pinfunction "V-_6") (pintype "bidirectional"))
    )
    (net (code "50") (name "Net-(PWR-PadA)") (class "Default")
      (node (ref "PWR") (pin "A") (pinfunction "A_A") (pintype "passive"))
      (node (ref "R4") (pin "1") (pinfunction "1_1") (pintype "passive"))
    )
    (net (code "51") (name "Net-(R1-Pad1)") (class "Default")
      (node (ref "R1") (pin "1") (pinfunction "1_1") (pintype "passive"))
      (node (ref "R3") (pin "1") (pinfunction "1_1") (pintype "passive"))
      (node (ref "X1") (pin "D-") (pinfunction "D-_D-") (pintype "bidirectional"))
    )
    (net (code "52") (name "Net-(R2-Pad1)") (class "Default")
      (node (ref "R2") (pin "1") (pinfunction "1_1") (pintype "passive"))
      (node (ref "X1") (pin "D+") (pinfunction "D+_D+") (pintype "bidirectional"))
    )
    (net (code "53") (name "Net-(R10-Pad2)") (class "Default")
      (node (ref "R10") (pin "2") (pinfunction "2_2") (pintype "passive"))
      (node (ref "SV1") (pin "4") (pinfunction "4_4") (pintype "passive"))
    )
    (net (code "54") (name "Net-(R11-Pad2)") (class "Default")
      (node (ref "R11") (pin "2") (pinfunction "2_2") (pintype "passive"))
      (node (ref "SV1") (pin "2") (pinfunction "2_2") (pintype "passive"))
    )
    (net (code "55") (name "Net-(R12-Pad2)") (class "Default")
      (node (ref "R12") (pin "2") (pinfunction "2_2") (pintype "passive"))
      (node (ref "SV1") (pin "1") (pinfunction "1_1") (pintype "passive"))
    )
    (net (code "56") (name "Net-(R13-Pad2)") (class "Default")
      (node (ref "R13") (pin "2") (pinfunction "2_2") (pintype "passive"))
      (node (ref "SV1") (pin "3") (pinfunction "3_3") (pintype "passive"))
    )
    (net (code "57") (name "Net-(R14-Pad2)") (class "Default")
      (node (ref "R14") (pin "2") (pinfunction "2_2") (pintype "passive"))
      (node (ref "SV1") (pin "5") (pinfunction "5_5") (pintype "passive"))
    )
    (net (code "58") (name "Net-(R20-Pad2)") (class "Default")
      (node (ref "R20") (pin "2") (pinfunction "2_2") (pintype "passive"))
      (node (ref "SV2") (pin "4") (pinfunction "4_4") (pintype "passive"))
    )
    (net (code "59") (name "Net-(R21-Pad2)") (class "Default")
      (node (ref "R21") (pin "2") (pinfunction "2_2") (pintype "passive"))
      (node (ref "SV2") (pin "2") (pinfunction "2_2") (pintype "passive"))
    )
    (net (code "60") (name "Net-(R22-Pad2)") (class "Default")
      (node (ref "R22") (pin "2") (pinfunction "2_2") (pintype "passive"))
      (node (ref "SV2") (pin "1") (pinfunction "1_1") (pintype "passive"))
    )
    (net (code "61") (name "Net-(R23-Pad2)") (class "Default")
      (node (ref "R23") (pin "2") (pinfunction "2_2") (pintype "passive"))
      (node (ref "SV2") (pin "3") (pinfunction "3_3") (pintype "passive"))
    )
    (net (code "62") (name "Net-(R24-Pad2)") (class "Default")
      (node (ref "R24") (pin "2") (pinfunction "2_2") (pintype "passive"))
      (node (ref "SV2") (pin "5") (pinfunction "5_5") (pintype "passive"))
    )
    (net (code "63") (name "Net-(S1B-S)") (class "Default")
      (node (ref "C12") (pin "2") (pinfunction "2_2") (pintype "passive"))
      (node (ref "JP3") (pin "2") (pinfunction "2_2") (pintype "passive"))
      (node (ref "S1") (pin "4") (pinfunction "S_4") (pintype "passive"))
      (node (ref "U$6") (pin "3") (pinfunction "BAT_3") (pintype "bidirectional"))
    )
    (net (code "64") (name "Net-(U$6-PROG)") (class "Default")
      (node (ref "R7") (pin "1") (pinfunction "1_1") (pintype "passive"))
      (node (ref "U$6") (pin "5") (pinfunction "PROG_5") (pintype "bidirectional"))
    )
    (net (code "65") (name "Net-(U$6-STAT)") (class "Default")
      (node (ref "R8") (pin "1") (pinfunction "1_1") (pintype "passive"))
      (node (ref "U$6") (pin "1") (pinfunction "STAT_1") (pintype "bidirectional"))
    )
    (net (code "66") (name "Net-(U$7-C1)") (class "Default")
      (node (ref "D1") (pin "K") (pinfunction "K_K") (pintype "output"))
      (node (ref "U$7") (pin "1") (pinfunction "C1_1") (pintype "bidirectional"))
    )
    (net (code "67") (name "Net-(U$7-C2)") (class "Default")
      (node (ref "D4") (pin "K") (pinfunction "K_K") (pintype "output"))
      (node (ref "U$7") (pin "2") (pinfunction "C2_2") (pintype "bidirectional"))
    )
    (net (code "68") (name "Net-(U$7-C3)") (class "Default")
      (node (ref "D5") (pin "K") (pinfunction "K_K") (pintype "output"))
      (node (ref "U$7") (pin "3") (pinfunction "C3_3") (pintype "bidirectional"))
    )
    (net (code "69") (name "Net-(U$7-C4)") (class "Default")
      (node (ref "D6") (pin "K") (pinfunction "K_K") (pintype "output"))
      (node (ref "U$7") (pin "4") (pinfunction "C4_4") (pintype "bidirectional"))
    )
    (net (code "70") (name "VBAT") (class "Default")
      (node (ref "D3") (pin "A") (pinfunction "A_A") (pintype "passive"))
      (node (ref "JP1") (pin "1") (pinfunction "1_1") (pintype "passive"))
      (node (ref "S1") (pin "5") (pinfunction "P_5") (pintype "passive"))
    )
    (net (code "71") (name "VBUS") (class "Default")
      (node (ref "D2") (pin "A") (pinfunction "A_A") (pintype "passive"))
      (node (ref "FTDI") (pin "3") (pinfunction "3_3") (pintype "passive"))
      (node (ref "JP1") (pin "3") (pinfunction "3_3") (pintype "passive"))
      (node (ref "U$6") (pin "4") (pinfunction "VDD_4") (pintype "bidirectional"))
      (node (ref "X1") (pin "VBUS") (pinfunction "VBUS_VBUS") (pintype "power_in"))
    )
    (net (code "72") (name "unconnected-(IC2-BYP-Pad4)") (class "Default")
      (node (ref "IC2") (pin "4") (pinfunction "BYP_4") (pintype "bidirectional"))
    )
    (net (code "73") (name "unconnected-(IC3-~{INT}-Pad13)") (class "Default")
      (node (ref "IC3") (pin "13") (pinfunction "~{INT}_13") (pintype "bidirectional"))
    )
    (net (code "74") (name "unconnected-(IC4-R1IN-Pad13)") (class "Default")
      (node (ref "IC4") (pin "13") (pinfunction "R1IN_13") (pintype "output"))
    )
    (net (code "75") (name "unconnected-(IC4-R1OUT-Pad12)") (class "Default")
      (node (ref "IC4") (pin "12") (pinfunction "R1OUT_12") (pintype "input"))
    )
    (net (code "76") (name "unconnected-(IC4-T1IN-Pad11)") (class "Default")
      (node (ref "IC4") (pin "11") (pinfunction "T1IN_11") (pintype "input"))
    )
    (net (code "77") (name "unconnected-(IC4-T1OUT-Pad14)") (class "Default")
      (node (ref "IC4") (pin "14") (pinfunction "T1OUT_14") (pintype "output"))
    )
    (net (code "78") (name "unconnected-(S1A-O-Pad3)") (class "Default")
      (node (ref "S1") (pin "3") (pinfunction "O_3") (pintype "passive"))
    )
    (net (code "79") (name "unconnected-(S1A-P-Pad2)") (class "Default")
      (node (ref "S1") (pin "2") (pinfunction "P_2") (pintype "passive"))
    )
    (net (code "80") (name "unconnected-(S1A-S-Pad1)") (class "Default")
      (node (ref "S1") (pin "1") (pinfunction "S_1") (pintype "passive"))
    )
    (net (code "81") (name "unconnected-(S1B-O-Pad6)") (class "Default")
      (node (ref "S1") (pin "6") (pinfunction "O_6") (pintype "passive"))
    )
    (net (code "82") (name "unconnected-(U$5-D{slash}~{C}-Pad4)") (class "Default")
      (node (ref "U$5") (pin "4") (pinfunction "D/~{C}_4") (pintype "bidirectional"))
    )
    (net (code "83") (name "unconnected-(U$5-~{CS}-Pad6)") (class "Default")
      (node (ref "U$5") (pin "6") (pinfunction "~{CS}_6") (pintype "bidirectional"))
    )
    (net (code "84") (name "unconnected-(X1-PadID)") (class "Default")
      (node (ref "X1") (pin "ID") (pinfunction "ID_ID") (pintype "bidirectional"))
    )
  )
)
